# Eye-of-Ord-v1_8.net
KiCad netlist of a schematic drawn in EAGLE
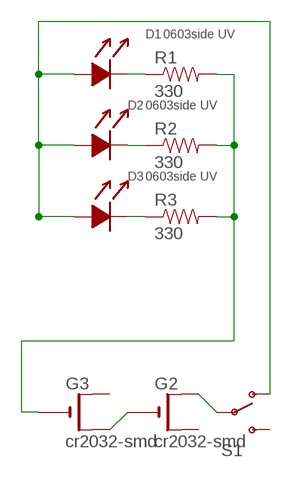
[diagram p0: schematic, sheet 1]

(export (version "E")
  (design (tool "Eeschema 10.0.6"))
  (components
    (comp (ref "D1")
      (value "0603side UV")
      (footprint "eagle-import:SMD-0603-LED-SIDE")
      (libsource (lib "eagle-import") (part "0603SIDELED"))
    )
    (comp (ref "D2")
      (value "0603side UV")
      (footprint "eagle-import:SMD-0603-LED-SIDE")
      (libsource (lib "eagle-import") (part "0603SIDELED"))
    )
    (comp (ref "D3")
      (value "0603side UV")
      (footprint "eagle-import:SMD-0603-LED-SIDE")
      (libsource (lib "eagle-import") (part "0603SIDELED"))
    )
    (comp (ref "G2")
      (value "cr2032-smd")
      (footprint "eagle-import:CR2032-SMD")
      (libsource (lib "eagle-import") (part "CR2032SMT"))
    )
    (comp (ref "G3")
      (value "cr2032-smd")
      (footprint "eagle-import:CR2032-SMD")
      (libsource (lib "eagle-import") (part "CR2032SMT"))
    )
    (comp (ref "R1")
      (value "330")
      (footprint "eagle-import:0603-RES")
      (libsource (lib "eagle-import") (part "RESISTOR0603-RES"))
    )
    (comp (ref "R2")
      (value "330")
      (footprint "eagle-import:0603-RES")
      (libsource (lib "eagle-import") (part "RESISTOR0603-RES"))
    )
    (comp (ref "R3")
      (value "330")
      (footprint "eagle-import:0603-RES")
      (libsource (lib "eagle-import") (part "RESISTOR0603-RES"))
    )
    (comp (ref "S1")
      (value "SWITCH-SPDT-SMD-A")
      (footprint "eagle-import:SWITCH-SPST-SMD-A")
      (libsource (lib "eagle-import") (part "SWITCH-SPDT-SMD-A"))
    )
  )
  (nets
    (net (code "1") (name "Net-(D1-K)") (class "Default")
      (node (ref "D1") (pin "C") (pinfunction "K_C") (pintype "bidirectional"))
      (node (ref "R1") (pin "1") (pinfunction "1_1") (pintype "passive"))
    )
    (net (code "2") (name "Net-(D2-K)") (class "Default")
      (node (ref "D2") (pin "C") (pinfunction "K_C") (pintype "bidirectional"))
      (node (ref "R2") (pin "1") (pinfunction "1_1") (pintype "passive"))
    )
    (net (code "3") (name "Net-(D3-K)") (class "Default")
      (node (ref "D3") (pin "C") (pinfunction "K_C") (pintype "bidirectional"))
      (node (ref "R3") (pin "1") (pinfunction "1_1") (pintype "passive"))
    )
    (net (code "4") (name "Net-(G2-+)") (class "Default")
      (node (ref "G2") (pin "+$1") (pinfunction "+_+$1") (pintype "passive"))
      (node (ref "S1") (pin "2") (pinfunction "P_2") (pintype "passive"))
    )
    (net (code "5") (name "Net-(G3-+1)") (class "Default")
      (node (ref "G2") (pin "-") (pinfunction "-_-") (pintype "passive"))
      (node (ref "G3") (pin "+$2") (pinfunction "+1_+$2") (pintype "passive"))
    )
    (net (code "6") (name "Net-(G3-Pad-)") (class "Default")
      (node (ref "G3") (pin "-") (pinfunction "-_-") (pintype "passive"))
      (node (ref "R1") (pin "2") (pinfunction "2_2") (pintype "passive"))
      (node (ref "R2") (pin "2") (pinfunction "2_2") (pintype "passive"))
      (node (ref "R3") (pin "2") (pinfunction "2_2") (pintype "passive"))
    )
    (net (code "7") (name "Net-(S1-O)") (class "Default")
      (node (ref "D1") (pin "A") (pinfunction "A_A") (pintype "bidirectional"))
      (node (ref "D2") (pin "A") (pinfunction "A_A") (pintype "bidirectional"))
      (node (ref "D3") (pin "A") (pinfunction "A_A") (pintype "bidirectional"))
      (node (ref "S1") (pin "1") (pinfunction "O_1") (pintype "passive"))
    )
    (net (code "8") (name "unconnected-(G2-+1-Pad+$2)") (class "Default")
      (node (ref "G2") (pin "+$2") (pinfunction "+1_+$2") (pintype "passive"))
    )
    (net (code "9") (name "unconnected-(G3-+-Pad+$1)") (class "Default")
      (node (ref "G3") (pin "+$1") (pinfunction "+_+$1") (pintype "passive"))
    )
    (net (code "10") (name "unconnected-(S1-S-Pad3)") (class "Default")
      (node (ref "S1") (pin "3") (pinfunction "S_3") (pintype "passive"))
    )
  )
)
